# main.net
KiCad netlist of a schematic drawn in Altium Designer
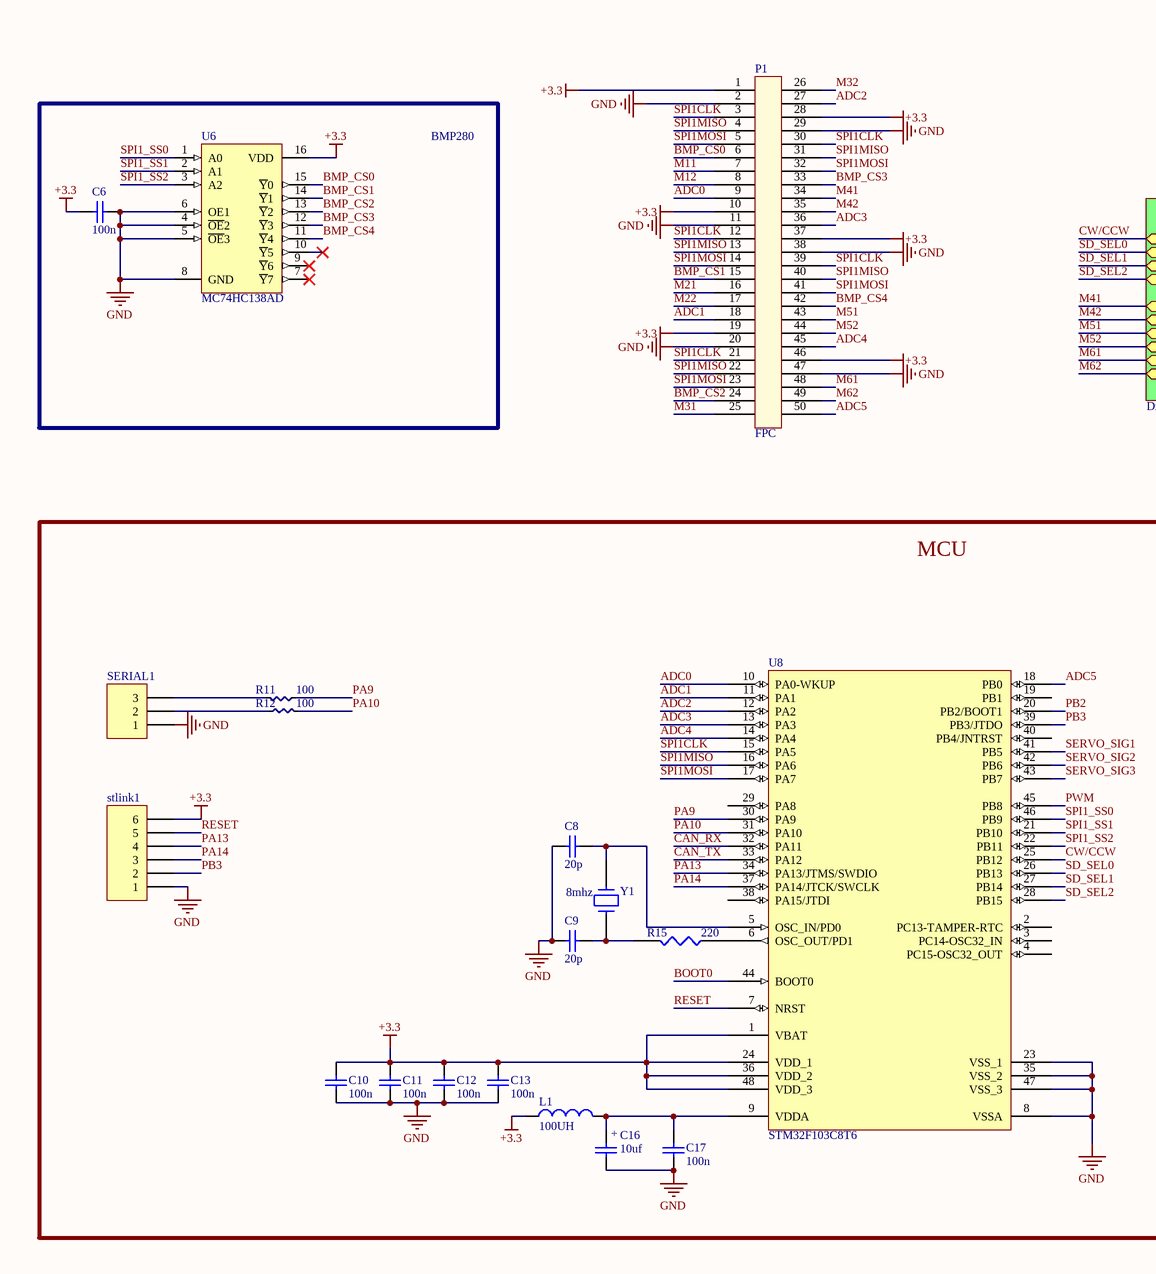
[diagram p0: main.SchDoc, left]
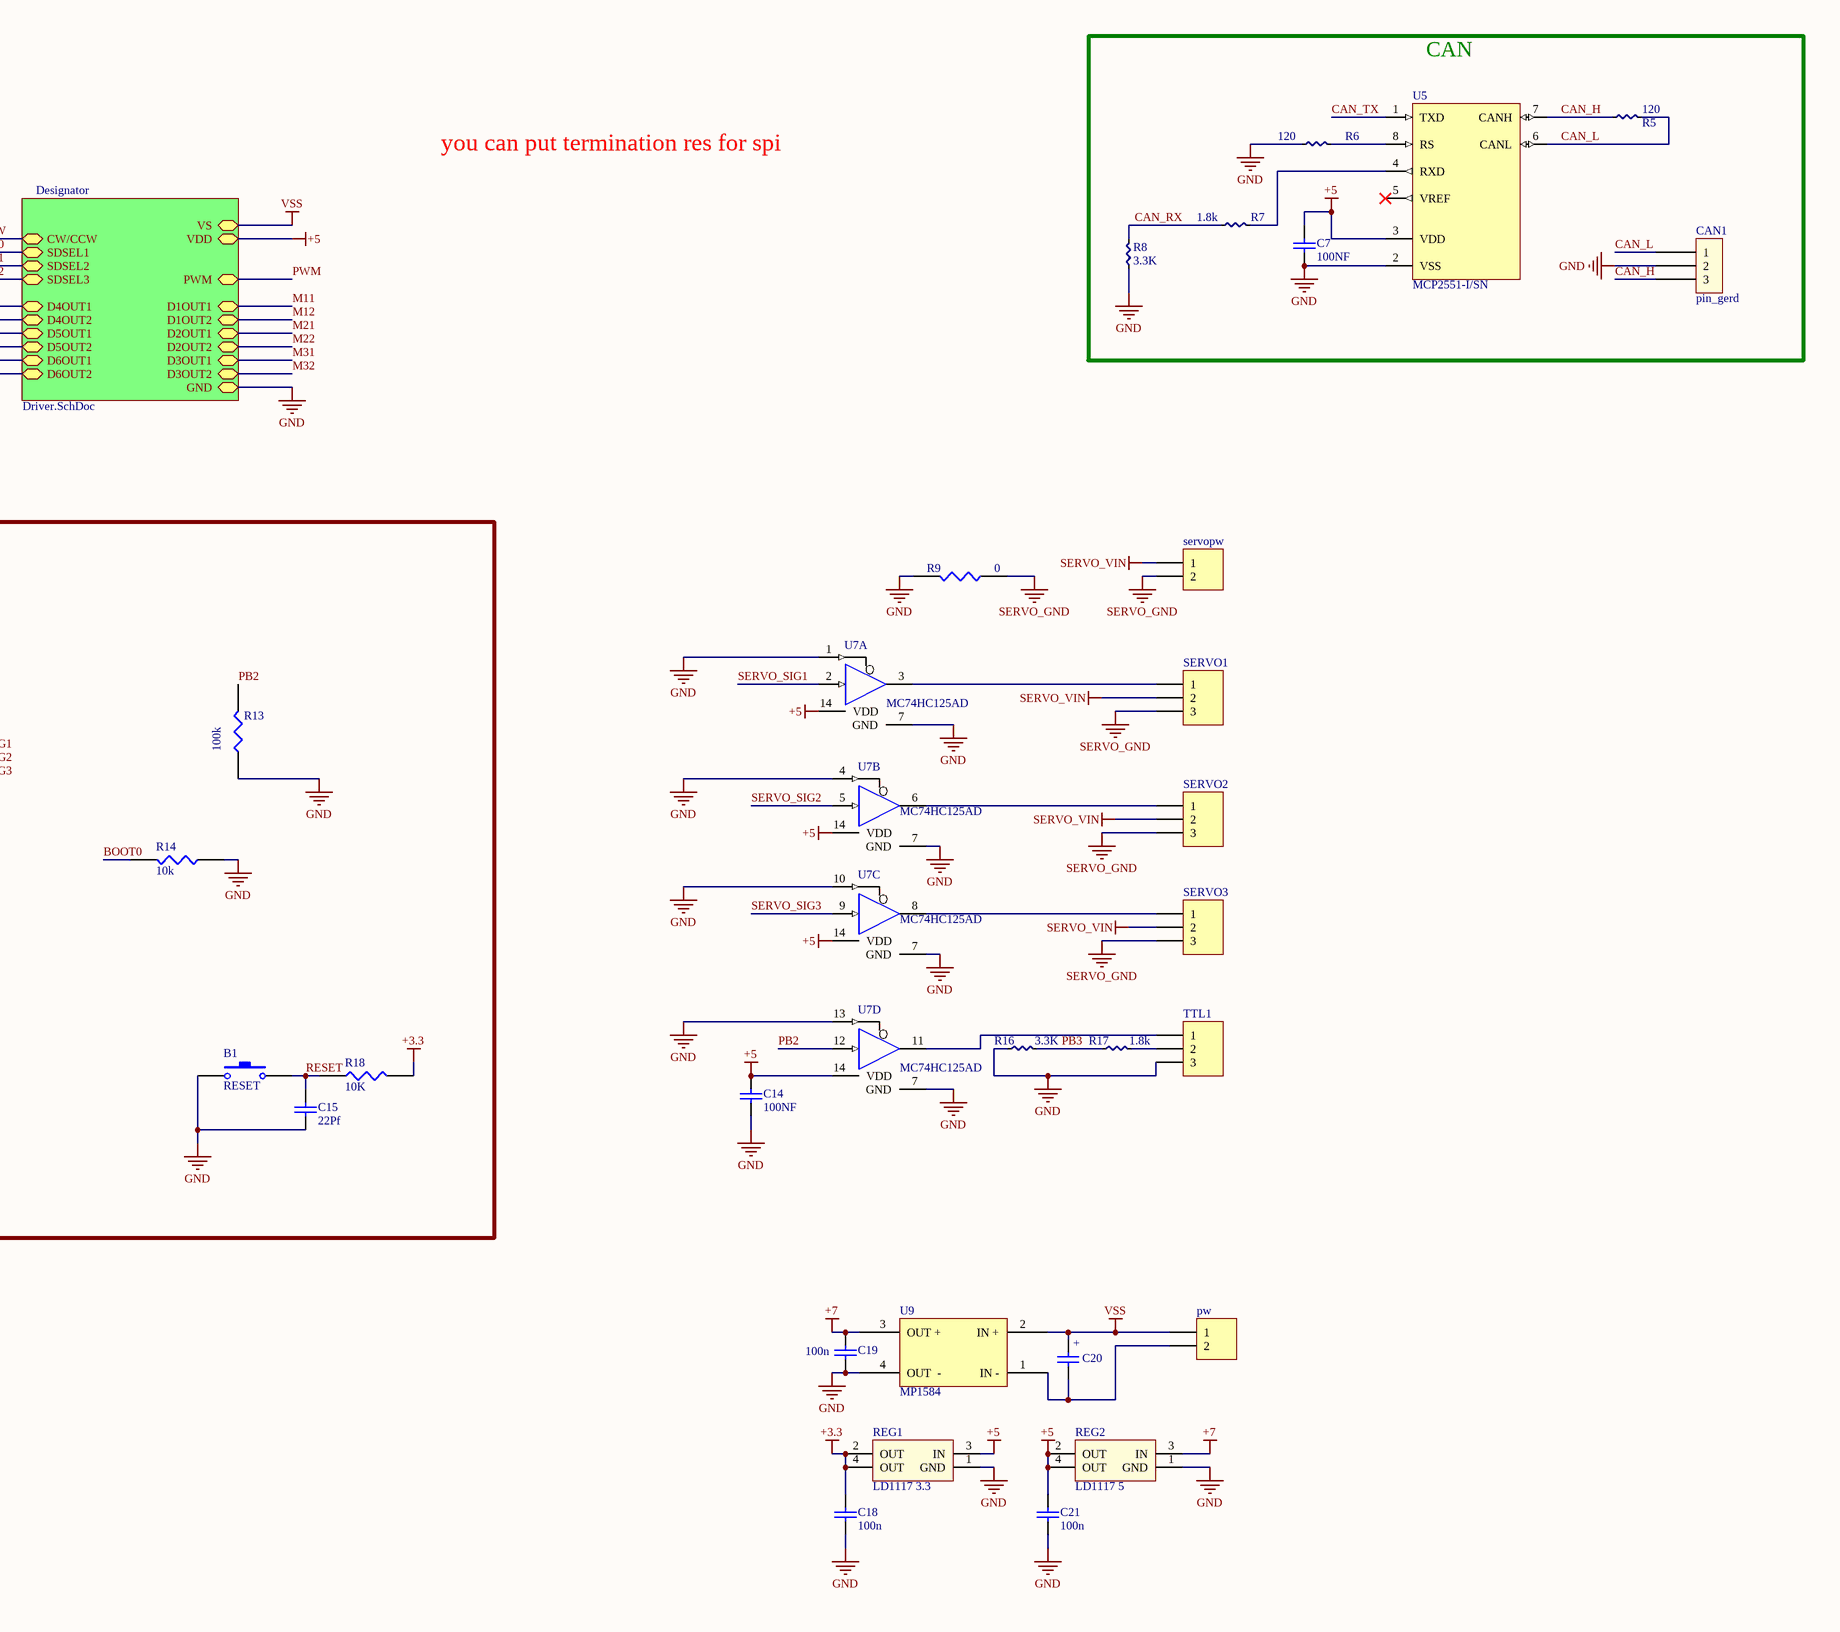
[diagram p1: main.SchDoc, right]

(export (version "E")
  (design (tool "Eeschema 10.0.6"))
  (components
    (comp (ref "B1")
      (value "RESET")
      (footprint "SMD PUSH BUTTON")
      (libsource (lib "AMINLIB") (part "SMD_PUSH_BUTTON"))
    )
    (comp (ref "C6")
      (value "100n")
      (footprint "MY_CAP_SMD_0805")
      (libsource (lib "AMINLIB") (part "CAP SMD"))
    )
    (comp (ref "C7")
      (value "100NF")
      (footprint "MY_CAP_SMD_0805")
      (description "2.0 mm × 1.25 mm")
      (libsource (lib "AMINLIB") (part "CAP SMD_0805"))
    )
    (comp (ref "C8") (value "20p") (footprint "MY_CAP_SMD_0805") (libsource (lib "AMINLIB") (part "CAP SMD")))
    (comp (ref "C9") (value "20p") (footprint "MY_CAP_SMD_0805") (libsource (lib "AMINLIB") (part "CAP SMD")))
    (comp (ref "C10")
      (value "100n")
      (footprint "MY_CAP_SMD_0805")
      (libsource (lib "AMINLIB") (part "CAP SMD"))
    )
    (comp (ref "C11")
      (value "100n")
      (footprint "MY_CAP_SMD_0805")
      (libsource (lib "AMINLIB") (part "CAP SMD"))
    )
    (comp (ref "C12")
      (value "100n")
      (footprint "MY_CAP_SMD_0805")
      (libsource (lib "AMINLIB") (part "CAP SMD"))
    )
    (comp (ref "C13")
      (value "100n")
      (footprint "MY_CAP_SMD_0805")
      (libsource (lib "AMINLIB") (part "CAP SMD"))
    )
    (comp (ref "C14")
      (value "100NF")
      (footprint "MY_CAP_SMD_0805")
      (description "2.0 mm × 1.25 mm")
      (libsource (lib "AMINLIB") (part "CAP SMD_0805"))
    )
    (comp (ref "C15")
      (value "22Pf")
      (footprint "MY_CAP_SMD_0805")
      (libsource (lib "AMINLIB") (part "CAP SMD"))
    )
    (comp (ref "C16")
      (value "10uf")
      (footprint "MY_cap_smd10uf")
      (libsource (lib "AMINLIB") (part "cap_smd_10u"))
    )
    (comp (ref "C17")
      (value "100n")
      (footprint "MY_CAP_SMD_0805")
      (libsource (lib "AMINLIB") (part "CAP SMD"))
    )
    (comp (ref "C18")
      (value "100n")
      (footprint "MY_CAP_SMD_0805")
      (libsource (lib "AMINLIB") (part "CAP SMD"))
    )
    (comp (ref "C19")
      (value "100n")
      (footprint "MY_CAP_SMD_0805")
      (libsource (lib "AMINLIB") (part "CAP SMD"))
    )
    (comp (ref "C20")
      (value "Cap")
      (footprint "MY_CAP_SMD-C")
      (description "6X3.2MM")
      (libsource (lib "AMINLIB") (part "CAP_TANTAL_C"))
    )
    (comp (ref "C21")
      (value "100n")
      (footprint "MY_CAP_SMD_0805")
      (libsource (lib "AMINLIB") (part "CAP SMD"))
    )
    (comp (ref "CAN1")
      (value "pin_gerd")
      (footprint "MY_PINGERD3")
      (description "3pin")
      (libsource (lib "AMINLIB") (part "pin_gerd"))
    )
    (comp (ref "L1")
      (value "100UH")
      (footprint "MY_SMD_INDUCTOR")
      (libsource (lib "AMINLIB") (part "INDUCTOR SMD"))
    )
    (comp (ref "P1")
      (value "FPC")
      (footprint "FPC-50-POS-0.5-MM")
      (libsource (lib "HAND-MULTILAYER") (part "FPC-50-POS-0.5-MM"))
    )
    (comp (ref "pw")
      (value "Header 2")
      (footprint "My_1X02")
      (description "Header, 2-Pin")
      (fields (field (name "PUBLISHER") "Altium Limited"))
      (libsource (lib "AMINLIB") (part "Header 2"))
    )
    (comp (ref "R5")
      (value "120")
      (footprint "MY_RES_SMD_0805")
      (libsource (lib "AMINLIB") (part "RES SMD 0805"))
    )
    (comp (ref "R6")
      (value "120")
      (footprint "MY_RES_SMD_0805")
      (libsource (lib "AMINLIB") (part "RES SMD 0805"))
    )
    (comp (ref "R7")
      (value "1.8k")
      (footprint "MY_RES_SMD_0805")
      (libsource (lib "AMINLIB") (part "RES SMD 0805"))
    )
    (comp (ref "R8")
      (value "3.3K")
      (footprint "MY_RES_SMD_0805")
      (libsource (lib "AMINLIB") (part "RES SMD 0805"))
    )
    (comp (ref "R9") (value "0") (footprint "MY_RES_SMD_0805") (libsource (lib "AMINLIB") (part "RES SMD")))
    (comp (ref "R11")
      (value "100")
      (footprint "MY_RES_SMD_0805")
      (libsource (lib "AMINLIB") (part "RES SMD 0805"))
    )
    (comp (ref "R12")
      (value "100")
      (footprint "MY_RES_SMD_0805")
      (libsource (lib "AMINLIB") (part "RES SMD 0805"))
    )
    (comp (ref "R13")
      (value "100k")
      (footprint "MY_RES_SMD_0805")
      (libsource (lib "AMINLIB") (part "RES SMD"))
    )
    (comp (ref "R14")
      (value "10k")
      (footprint "MY_RES_SMD_0805")
      (libsource (lib "AMINLIB") (part "RES SMD"))
    )
    (comp (ref "R15")
      (value "220")
      (footprint "MY_RES_SMD_0805")
      (libsource (lib "AMINLIB") (part "RES SMD"))
    )
    (comp (ref "R16")
      (value "3.3K")
      (footprint "MY_RES_SMD_0805")
      (libsource (lib "AMINLIB") (part "RES SMD 0805"))
    )
    (comp (ref "R17")
      (value "1.8k")
      (footprint "MY_RES_SMD_0805")
      (libsource (lib "AMINLIB") (part "RES SMD 0805"))
    )
    (comp (ref "R18")
      (value "10K")
      (footprint "MY_RES_SMD_0805")
      (libsource (lib "AMINLIB") (part "RES SMD"))
    )
    (comp (ref "REG1")
      (value "LD1117 3.3")
      (footprint "MY_LD1117-3.3")
      (libsource (lib "AMINLIB") (part "LD1117 3.3"))
    )
    (comp (ref "REG2")
      (value "LD1117 5")
      (footprint "MY_LD1117-3.3")
      (libsource (lib "AMINLIB") (part "LD1117 3.3"))
    )
    (comp (ref "SERIAL1")
      (value "Header 3")
      (footprint "My_1X03")
      (description "Header, 3-Pin")
      (fields (field (name "PUBLISHER") "Altium Limited"))
      (libsource (lib "AMINLIB") (part "Header 3"))
    )
    (comp (ref "SERVO1")
      (value "Header 3")
      (footprint "My_1X03")
      (description "Header, 3-Pin")
      (fields (field (name "PUBLISHER") "Altium Limited"))
      (libsource (lib "") (part "Header 3_1"))
    )
    (comp (ref "SERVO2")
      (value "Header 3")
      (footprint "My_1X03")
      (description "Header, 3-Pin")
      (fields (field (name "PUBLISHER") "Altium Limited"))
      (libsource (lib "") (part "Header 3_1"))
    )
    (comp (ref "SERVO3")
      (value "Header 3")
      (footprint "My_1X03")
      (description "Header, 3-Pin")
      (fields (field (name "PUBLISHER") "Altium Limited"))
      (libsource (lib "") (part "Header 3_1"))
    )
    (comp (ref "servopw")
      (value "Header 2")
      (footprint "My_1X02")
      (description "Header, 2-Pin")
      (fields (field (name "PUBLISHER") "Altium Limited"))
      (libsource (lib "AMINLIB") (part "Header 2"))
    )
    (comp (ref "stlink1")
      (value "Header 6")
      (footprint "My_1X06")
      (description "Header, 6-Pin")
      (fields (field (name "PUBLISHER") "Altium Limited"))
      (libsource (lib "AMINLIB") (part "Header 6"))
    )
    (comp (ref "TTL1")
      (value "Header 3")
      (footprint "My_1X03")
      (description "Header, 3-Pin")
      (fields (field (name "PUBLISHER") "Altium Limited"))
      (libsource (lib "") (part "Header 3_1"))
    )
    (comp (ref "U5")
      (value "MCP2551-I/SN")
      (footprint "SOIC-SN8_N")
      (description "High-Speed CAN Transceiver, 8-Pin SOIC, Industrial Temperature")
      (fields (field (name "PUBLISHER") "Altium Limited"))
      (libsource (lib "Microchip Interface") (part "MCP2551-I/SN"))
    )
    (comp (ref "U6")
      (value "MC74HC138AD")
      (footprint "751B-03_N")
      (description "1-of-8 Decoder/Demultiplexer")
      (fields (field (name "PUBLISHER") "Altium Limited"))
      (libsource (lib "Motorola Logic Decoder Demux") (part "MC74HC138AD"))
    )
    (comp (ref "U7")
      (value "MC74HC125AD")
      (footprint "751A-02_N")
      (description "Quad 3-State Non-Inverting Buffer")
      (fields (field (name "PUBLISHER") "Altium Limited"))
      (libsource (lib "Motorola Logic Buffer Line Driver") (part "MC74HC125AD"))
    )
    (comp (ref "U8")
      (value "STM32F103C8T6")
      (footprint "LQFP48_N")
      (description "STM32 ARM-based 32-bit MCU with 64 Kbytes Flash, 48-pin LQFP, Industrial Temperature")
      (fields (field (name "PUBLISHER") "Altium Limited"))
      (libsource (lib "ST Microcontroller 32-Bit STM32") (part "STM32F103C8T6"))
    )
    (comp (ref "U9")
      (value "MP1584")
      (footprint "mp1584")
      (description "SWITCHING REGULATOR MODULE")
      (fields (field (name "PART") "MP1584EN-LF-Z"))
      (libsource (lib "AMINLIB") (part "MP1584"))
    )
    (comp (ref "Y1")
      (value "8mhz")
      (footprint "My_Crystal - SMD")
      (description "Crystal")
      (libsource (lib "AMINLIB") (part "CRYSTAL"))
    )
  )
  (nets
    (net (code "1") (name "+3.3") (class "Default")
      (node (ref "C10") (pin "2") (pinfunction "2_2") (pintype "passive"))
      (node (ref "C11") (pin "2") (pinfunction "2_2") (pintype "passive"))
      (node (ref "C12") (pin "2") (pinfunction "2_2") (pintype "passive"))
      (node (ref "C13") (pin "2") (pinfunction "2_2") (pintype "passive"))
      (node (ref "C18") (pin "2") (pinfunction "2_2") (pintype "passive"))
      (node (ref "C6") (pin "2") (pinfunction "2_2") (pintype "passive"))
      (node (ref "L1") (pin "1") (pinfunction "1_1") (pintype "passive"))
      (node (ref "P1") (pin "1") (pinfunction "1_1") (pintype "passive"))
      (node (ref "P1") (pin "10") (pinfunction "10_10") (pintype "passive"))
      (node (ref "P1") (pin "19") (pinfunction "19_19") (pintype "passive"))
      (node (ref "P1") (pin "28") (pinfunction "28_28") (pintype "passive"))
      (node (ref "P1") (pin "37") (pinfunction "37_37") (pintype "passive"))
      (node (ref "P1") (pin "46") (pinfunction "46_46") (pintype "passive"))
      (node (ref "R18") (pin "2") (pinfunction "2_2") (pintype "passive"))
      (node (ref "REG1") (pin "2") (pinfunction "OUT_2") (pintype "power_in"))
      (node (ref "REG1") (pin "4") (pinfunction "OUT_4") (pintype "power_in"))
      (node (ref "U6") (pin "16") (pinfunction "VDD_16") (pintype "power_in"))
      (node (ref "U8") (pin "1") (pinfunction "VBAT_1") (pintype "power_in"))
      (node (ref "U8") (pin "24") (pinfunction "VDD_1_24") (pintype "power_in"))
      (node (ref "U8") (pin "36") (pinfunction "VDD_2_36") (pintype "power_in"))
      (node (ref "U8") (pin "48") (pinfunction "VDD_3_48") (pintype "power_in"))
      (node (ref "stlink1") (pin "6") (pinfunction "6_6") (pintype "passive"))
    )
    (net (code "2") (name "+5") (class "Default")
      (node (ref "C14") (pin "2") (pinfunction "2_2") (pintype "passive"))
      (node (ref "C21") (pin "2") (pinfunction "2_2") (pintype "passive"))
      (node (ref "C7") (pin "2") (pinfunction "2_2") (pintype "passive"))
      (node (ref "REG1") (pin "3") (pinfunction "IN_3") (pintype "power_in"))
      (node (ref "REG2") (pin "2") (pinfunction "OUT_2") (pintype "power_in"))
      (node (ref "REG2") (pin "4") (pinfunction "OUT_4") (pintype "power_in"))
      (node (ref "U5") (pin "3") (pinfunction "VDD_3") (pintype "power_in"))
      (node (ref "U7") (pin "14") (pinfunction "VDD_14") (pintype "power_in"))
    )
    (net (code "3") (name "+7") (class "Default")
      (node (ref "C19") (pin "2") (pinfunction "2_2") (pintype "passive"))
      (node (ref "REG2") (pin "3") (pinfunction "IN_3") (pintype "power_in"))
      (node (ref "U9") (pin "3") (pinfunction "OUT_+_3") (pintype "passive"))
    )
    (net (code "4") (name "/ADC0") (class "Default")
      (node (ref "P1") (pin "9") (pinfunction "9_9") (pintype "passive"))
      (node (ref "U8") (pin "10") (pinfunction "PA0-WKUP_10") (pintype "bidirectional"))
    )
    (net (code "5") (name "/ADC1") (class "Default")
      (node (ref "P1") (pin "18") (pinfunction "18_18") (pintype "passive"))
      (node (ref "U8") (pin "11") (pinfunction "PA1_11") (pintype "bidirectional"))
    )
    (net (code "6") (name "/ADC2") (class "Default")
      (node (ref "P1") (pin "27") (pinfunction "27_27") (pintype "passive"))
      (node (ref "U8") (pin "12") (pinfunction "PA2_12") (pintype "bidirectional"))
    )
    (net (code "7") (name "/ADC3") (class "Default")
      (node (ref "P1") (pin "36") (pinfunction "36_36") (pintype "passive"))
      (node (ref "U8") (pin "13") (pinfunction "PA3_13") (pintype "bidirectional"))
    )
    (net (code "8") (name "/ADC4") (class "Default")
      (node (ref "P1") (pin "45") (pinfunction "45_45") (pintype "passive"))
      (node (ref "U8") (pin "14") (pinfunction "PA4_14") (pintype "bidirectional"))
    )
    (net (code "9") (name "/ADC5") (class "Default")
      (node (ref "P1") (pin "50") (pinfunction "50_50") (pintype "passive"))
      (node (ref "U8") (pin "18") (pinfunction "PB0_18") (pintype "bidirectional"))
    )
    (net (code "10") (name "/BMP_CS0") (class "Default")
      (node (ref "P1") (pin "6") (pinfunction "6_6") (pintype "passive"))
      (node (ref "U6") (pin "15") (pinfunction "~{Y}0_15") (pintype "output"))
    )
    (net (code "11") (name "/BMP_CS1") (class "Default")
      (node (ref "P1") (pin "15") (pinfunction "15_15") (pintype "passive"))
      (node (ref "U6") (pin "14") (pinfunction "~{Y}1_14") (pintype "output"))
    )
    (net (code "12") (name "/BMP_CS2") (class "Default")
      (node (ref "P1") (pin "24") (pinfunction "24_24") (pintype "passive"))
      (node (ref "U6") (pin "13") (pinfunction "~{Y}2_13") (pintype "output"))
    )
    (net (code "13") (name "/BMP_CS3") (class "Default")
      (node (ref "P1") (pin "33") (pinfunction "33_33") (pintype "passive"))
      (node (ref "U6") (pin "12") (pinfunction "~{Y}3_12") (pintype "output"))
    )
    (net (code "14") (name "/BMP_CS4") (class "Default")
      (node (ref "P1") (pin "42") (pinfunction "42_42") (pintype "passive"))
      (node (ref "U6") (pin "11") (pinfunction "~{Y}4_11") (pintype "output"))
    )
    (net (code "15") (name "/BOOT0") (class "Default")
      (node (ref "R14") (pin "2") (pinfunction "2_2") (pintype "passive"))
      (node (ref "U8") (pin "44") (pinfunction "BOOT0_44") (pintype "input"))
    )
    (net (code "16") (name "/CAN_H") (class "Default")
      (node (ref "CAN1") (pin "3") (pinfunction "3_3") (pintype "passive"))
      (node (ref "R5") (pin "1") (pinfunction "1_1") (pintype "passive"))
      (node (ref "U5") (pin "7") (pinfunction "CANH_7") (pintype "bidirectional"))
    )
    (net (code "17") (name "/CAN_L") (class "Default")
      (node (ref "CAN1") (pin "1") (pinfunction "1_1") (pintype "passive"))
      (node (ref "R5") (pin "2") (pinfunction "2_2") (pintype "passive"))
      (node (ref "U5") (pin "6") (pinfunction "CANL_6") (pintype "bidirectional"))
    )
    (net (code "18") (name "/CAN_RX") (class "Default")
      (node (ref "R7") (pin "1") (pinfunction "1_1") (pintype "passive"))
      (node (ref "R8") (pin "2") (pinfunction "2_2") (pintype "passive"))
      (node (ref "U8") (pin "32") (pinfunction "PA11_32") (pintype "bidirectional"))
    )
    (net (code "19") (name "/CAN_TX") (class "Default")
      (node (ref "U5") (pin "1") (pinfunction "TXD_1") (pintype "input"))
      (node (ref "U8") (pin "33") (pinfunction "PA12_33") (pintype "bidirectional"))
    )
    (net (code "20") (name "/CW{slash}CCW") (class "Default")
      (node (ref "U8") (pin "25") (pinfunction "PB12_25") (pintype "bidirectional"))
    )
    (net (code "21") (name "/M11") (class "Default")
      (node (ref "P1") (pin "7") (pinfunction "7_7") (pintype "passive"))
    )
    (net (code "22") (name "/M12") (class "Default")
      (node (ref "P1") (pin "8") (pinfunction "8_8") (pintype "passive"))
    )
    (net (code "23") (name "/M21") (class "Default")
      (node (ref "P1") (pin "16") (pinfunction "16_16") (pintype "passive"))
    )
    (net (code "24") (name "/M22") (class "Default")
      (node (ref "P1") (pin "17") (pinfunction "17_17") (pintype "passive"))
    )
    (net (code "25") (name "/M31") (class "Default")
      (node (ref "P1") (pin "25") (pinfunction "25_25") (pintype "passive"))
    )
    (net (code "26") (name "/M32") (class "Default")
      (node (ref "P1") (pin "26") (pinfunction "26_26") (pintype "passive"))
    )
    (net (code "27") (name "/M41") (class "Default")
      (node (ref "P1") (pin "34") (pinfunction "34_34") (pintype "passive"))
    )
    (net (code "28") (name "/M42") (class "Default")
      (node (ref "P1") (pin "35") (pinfunction "35_35") (pintype "passive"))
    )
    (net (code "29") (name "/M51") (class "Default")
      (node (ref "P1") (pin "43") (pinfunction "43_43") (pintype "passive"))
    )
    (net (code "30") (name "/M52") (class "Default")
      (node (ref "P1") (pin "44") (pinfunction "44_44") (pintype "passive"))
    )
    (net (code "31") (name "/M61") (class "Default")
      (node (ref "P1") (pin "48") (pinfunction "48_48") (pintype "passive"))
    )
    (net (code "32") (name "/M62") (class "Default")
      (node (ref "P1") (pin "49") (pinfunction "49_49") (pintype "passive"))
    )
    (net (code "33") (name "/PA9") (class "Default")
      (node (ref "R11") (pin "1") (pinfunction "1_1") (pintype "passive"))
      (node (ref "U8") (pin "30") (pinfunction "PA9_30") (pintype "bidirectional"))
    )
    (net (code "34") (name "/PA10") (class "Default")
      (node (ref "R12") (pin "2") (pinfunction "2_2") (pintype "passive"))
      (node (ref "U8") (pin "31") (pinfunction "PA10_31") (pintype "bidirectional"))
    )
    (net (code "35") (name "/PA13") (class "Default")
      (node (ref "U8") (pin "34") (pinfunction "PA13/JTMS/SWDIO_34") (pintype "bidirectional"))
      (node (ref "stlink1") (pin "4") (pinfunction "4_4") (pintype "passive"))
    )
    (net (code "36") (name "/PA14") (class "Default")
      (node (ref "U8") (pin "37") (pinfunction "PA14/JTCK/SWCLK_37") (pintype "bidirectional"))
      (node (ref "stlink1") (pin "3") (pinfunction "3_3") (pintype "passive"))
    )
    (net (code "37") (name "/PB2") (class "Default")
      (node (ref "R13") (pin "2") (pinfunction "2_2") (pintype "passive"))
      (node (ref "U7") (pin "12") (pinfunction "A_12") (pintype "input"))
      (node (ref "U8") (pin "20") (pinfunction "PB2/BOOT1_20") (pintype "bidirectional"))
    )
    (net (code "38") (name "/PB3") (class "Default")
      (node (ref "R16") (pin "2") (pinfunction "2_2") (pintype "passive"))
      (node (ref "R17") (pin "1") (pinfunction "1_1") (pintype "passive"))
      (node (ref "U8") (pin "39") (pinfunction "PB3/JTDO_39") (pintype "bidirectional"))
      (node (ref "stlink1") (pin "2") (pinfunction "2_2") (pintype "passive"))
    )
    (net (code "39") (name "/PWM") (class "Default")
      (node (ref "U8") (pin "45") (pinfunction "PB8_45") (pintype "bidirectional"))
    )
    (net (code "40") (name "/RESET") (class "Default")
      (node (ref "B1") (pin "2") (pinfunction "2_2") (pintype "passive"))
      (node (ref "C15") (pin "2") (pinfunction "2_2") (pintype "passive"))
      (node (ref "R18") (pin "1") (pinfunction "1_1") (pintype "passive"))
      (node (ref "U8") (pin "7") (pinfunction "NRST_7") (pintype "bidirectional"))
      (node (ref "stlink1") (pin "5") (pinfunction "5_5") (pintype "passive"))
    )
    (net (code "41") (name "/SD_SEL0") (class "Default")
      (node (ref "U8") (pin "26") (pinfunction "PB13_26") (pintype "bidirectional"))
    )
    (net (code "42") (name "/SD_SEL1") (class "Default")
      (node (ref "U8") (pin "27") (pinfunction "PB14_27") (pintype "bidirectional"))
    )
    (net (code "43") (name "/SD_SEL2") (class "Default")
      (node (ref "U8") (pin "28") (pinfunction "PB15_28") (pintype "bidirectional"))
    )
    (net (code "44") (name "/SERVO_SIG1") (class "Default")
      (node (ref "U7") (pin "2") (pinfunction "A_2") (pintype "input"))
      (node (ref "U8") (pin "41") (pinfunction "PB5_41") (pintype "bidirectional"))
    )
    (net (code "45") (name "/SERVO_SIG2") (class "Default")
      (node (ref "U7") (pin "5") (pinfunction "A_5") (pintype "input"))
      (node (ref "U8") (pin "42") (pinfunction "PB6_42") (pintype "bidirectional"))
    )
    (net (code "46") (name "/SERVO_SIG3") (class "Default")
      (node (ref "U7") (pin "9") (pinfunction "A_9") (pintype "input"))
      (node (ref "U8") (pin "43") (pinfunction "PB7_43") (pintype "bidirectional"))
    )
    (net (code "47") (name "/SPI1CLK") (class "Default")
      (node (ref "P1") (pin "12") (pinfunction "12_12") (pintype "passive"))
      (node (ref "P1") (pin "21") (pinfunction "21_21") (pintype "passive"))
      (node (ref "P1") (pin "3") (pinfunction "3_3") (pintype "passive"))
      (node (ref "P1") (pin "30") (pinfunction "30_30") (pintype "passive"))
      (node (ref "P1") (pin "39") (pinfunction "39_39") (pintype "passive"))
      (node (ref "U8") (pin "15") (pinfunction "PA5_15") (pintype "bidirectional"))
    )
    (net (code "48") (name "/SPI1MISO") (class "Default")
      (node (ref "P1") (pin "13") (pinfunction "13_13") (pintype "passive"))
      (node (ref "P1") (pin "22") (pinfunction "22_22") (pintype "passive"))
      (node (ref "P1") (pin "31") (pinfunction "31_31") (pintype "passive"))
      (node (ref "P1") (pin "4") (pinfunction "4_4") (pintype "passive"))
      (node (ref "P1") (pin "40") (pinfunction "40_40") (pintype "passive"))
      (node (ref "U8") (pin "16") (pinfunction "PA6_16") (pintype "bidirectional"))
    )
    (net (code "49") (name "/SPI1MOSI") (class "Default")
      (node (ref "P1") (pin "14") (pinfunction "14_14") (pintype "passive"))
      (node (ref "P1") (pin "23") (pinfunction "23_23") (pintype "passive"))
      (node (ref "P1") (pin "32") (pinfunction "32_32") (pintype "passive"))
      (node (ref "P1") (pin "41") (pinfunction "41_41") (pintype "passive"))
      (node (ref "P1") (pin "5") (pinfunction "5_5") (pintype "passive"))
      (node (ref "U8") (pin "17") (pinfunction "PA7_17") (pintype "bidirectional"))
    )
    (net (code "50") (name "/SPI1_SS0") (class "Default")
      (node (ref "U6") (pin "1") (pinfunction "A0_1") (pintype "input"))
      (node (ref "U8") (pin "46") (pinfunction "PB9_46") (pintype "bidirectional"))
    )
    (net (code "51") (name "/SPI1_SS1") (class "Default")
      (node (ref "U6") (pin "2") (pinfunction "A1_2") (pintype "input"))
      (node (ref "U8") (pin "21") (pinfunction "PB10_21") (pintype "bidirectional"))
    )
    (net (code "52") (name "/SPI1_SS2") (class "Default")
      (node (ref "U6") (pin "3") (pinfunction "A2_3") (pintype "input"))
      (node (ref "U8") (pin "22") (pinfunction "PB11_22") (pintype "bidirectional"))
    )
    (net (code "53") (name "GND") (class "Default")
      (node (ref "B1") (pin "1") (pinfunction "1_1") (pintype "passive"))
      (node (ref "C10") (pin "1") (pinfunction "1_1") (pintype "passive"))
      (node (ref "C11") (pin "1") (pinfunction "1_1") (pintype "passive"))
      (node (ref "C12") (pin "1") (pinfunction "1_1") (pintype "passive"))
      (node (ref "C13") (pin "1") (pinfunction "1_1") (pintype "passive"))
      (node (ref "C14") (pin "1") (pinfunction "1_1") (pintype "passive"))
      (node (ref "C15") (pin "1") (pinfunction "1_1") (pintype "passive"))
      (node (ref "C16") (pin "-") (pinfunction "-_-") (pintype "passive"))
      (node (ref "C17") (pin "1") (pinfunction "1_1") (pintype "passive"))
      (node (ref "C18") (pin "1") (pinfunction "1_1") (pintype "passive"))
      (node (ref "C19") (pin "1") (pinfunction "1_1") (pintype "passive"))
      (node (ref "C21") (pin "1") (pinfunction "1_1") (pintype "passive"))
      (node (ref "C6") (pin "1") (pinfunction "1_1") (pintype "passive"))
      (node (ref "C7") (pin "1") (pinfunction "1_1") (pintype "passive"))
      (node (ref "C8") (pin "2") (pinfunction "2_2") (pintype "passive"))
      (node (ref "C9") (pin "1") (pinfunction "1_1") (pintype "passive"))
      (node (ref "CAN1") (pin "2") (pinfunction "2_2") (pintype "passive"))
      (node (ref "P1") (pin "11") (pinfunction "11_11") (pintype "passive"))
      (node (ref "P1") (pin "2") (pinfunction "2_2") (pintype "passive"))
      (node (ref "P1") (pin "20") (pinfunction "20_20") (pintype "passive"))
      (node (ref "P1") (pin "29") (pinfunction "29_29") (pintype "passive"))
      (node (ref "P1") (pin "38") (pinfunction "38_38") (pintype "passive"))
      (node (ref "P1") (pin "47") (pinfunction "47_47") (pintype "passive"))
      (node (ref "R13") (pin "1") (pinfunction "1_1") (pintype "passive"))
      (node (ref "R14") (pin "1") (pinfunction "1_1") (pintype "passive"))
      (node (ref "R16") (pin "1") (pinfunction "1_1") (pintype "passive"))
      (node (ref "R6") (pin "1") (pinfunction "1_1") (pintype "passive"))
      (node (ref "R8") (pin "1") (pinfunction "1_1") (pintype "passive"))
      (node (ref "R9") (pin "2") (pinfunction "2_2") (pintype "passive"))
      (node (ref "REG1") (pin "1") (pinfunction "GND_1") (pintype "power_in"))
      (node (ref "REG2") (pin "1") (pinfunction "GND_1") (pintype "power_in"))
      (node (ref "SERIAL1") (pin "1") (pinfunction "1_1") (pintype "passive"))
      (node (ref "TTL1") (pin "3") (pinfunction "3_3") (pintype "passive"))
      (node (ref "U5") (pin "2") (pinfunction "VSS_2") (pintype "power_in"))
      (node (ref "U6") (pin "4") (pinfunction "~{OE}2_4") (pintype "input"))
      (node (ref "U6") (pin "5") (pinfunction "~{OE}3_5") (pintype "input"))
      (node (ref "U6") (pin "6") (pinfunction "OE1_6") (pintype "input"))
      (node (ref "U6") (pin "8") (pinfunction "GND_8") (pintype "power_in"))
      (node (ref "U7") (pin "1") (pinfunction "~{OE}_1") (pintype "input"))
      (node (ref "U7") (pin "10") (pinfunction "~{OE}_10") (pintype "input"))
      (node (ref "U7") (pin "13") (pinfunction "~{OE}_13") (pintype "input"))
      (node (ref "U7") (pin "4") (pinfunction "~{OE}_4") (pintype "input"))
      (node (ref "U7") (pin "7") (pinfunction "GND_7") (pintype "power_in"))
      (node (ref "U8") (pin "23") (pinfunction "VSS_1_23") (pintype "power_in"))
      (node (ref "U8") (pin "35") (pinfunction "VSS_2_35") (pintype "power_in"))
      (node (ref "U8") (pin "47") (pinfunction "VSS_3_47") (pintype "power_in"))
      (node (ref "U8") (pin "8") (pinfunction "VSSA_8") (pintype "power_in"))
      (node (ref "U9") (pin "4") (pinfunction "OUT__-_4") (pintype "passive"))
      (node (ref "stlink1") (pin "1") (pinfunction "1_1") (pintype "passive"))
    )
    (net (code "54") (name "Net-(C9-Pad2)") (class "Default")
      (node (ref "C9") (pin "2") (pinfunction "2_2") (pintype "passive"))
      (node (ref "R15") (pin "2") (pinfunction "2_2") (pintype "passive"))
      (node (ref "Y1") (pin "1") (pinfunction "1_1") (pintype "passive"))
    )
    (net (code "55") (name "Net-(R11-Pad2)") (class "Default")
      (node (ref "R11") (pin "2") (pinfunction "2_2") (pintype "passive"))
      (node (ref "SERIAL1") (pin "3") (pinfunction "3_3") (pintype "passive"))
    )
    (net (code "56") (name "Net-(R12-Pad1)") (class "Default")
      (node (ref "R12") (pin "1") (pinfunction "1_1") (pintype "passive"))
      (node (ref "SERIAL1") (pin "2") (pinfunction "2_2") (pintype "passive"))
    )
    (net (code "57") (name "Net-(R17-Pad2)") (class "Default")
      (node (ref "R17") (pin "2") (pinfunction "2_2") (pintype "passive"))
      (node (ref "TTL1") (pin "2") (pinfunction "2_2") (pintype "passive"))
    )
    (net (code "58") (name "Net-(U5-RS)") (class "Default")
      (node (ref "R6") (pin "2") (pinfunction "2_2") (pintype "passive"))
      (node (ref "U5") (pin "8") (pinfunction "RS_8") (pintype "input"))
    )
    (net (code "59") (name "Net-(U5-RXD)") (class "Default")
      (node (ref "R7") (pin "2") (pinfunction "2_2") (pintype "passive"))
      (node (ref "U5") (pin "4") (pinfunction "RXD_4") (pintype "output"))
    )
    (net (code "60") (name "Net-(U7A-Y)") (class "Default")
      (node (ref "SERVO1") (pin "1") (pinfunction "1_1") (pintype "passive"))
      (node (ref "U7") (pin "3") (pinfunction "Y_3") (pintype "tri_state"))
    )
    (net (code "61") (name "Net-(U7B-Y)") (class "Default")
      (node (ref "SERVO2") (pin "1") (pinfunction "1_1") (pintype "passive"))
      (node (ref "U7") (pin "6") (pinfunction "Y_6") (pintype "tri_state"))
    )
    (net (code "62") (name "Net-(U7C-Y)") (class "Default")
      (node (ref "SERVO3") (pin "1") (pinfunction "1_1") (pintype "passive"))
      (node (ref "U7") (pin "8") (pinfunction "Y_8") (pintype "tri_state"))
    )
    (net (code "63") (name "Net-(U7D-Y)") (class "Default")
      (node (ref "TTL1") (pin "1") (pinfunction "1_1") (pintype "passive"))
      (node (ref "U7") (pin "11") (pinfunction "Y_11") (pintype "tri_state"))
    )
    (net (code "64") (name "Net-(U8-OSC_IN{slash}PD0)") (class "Default")
      (node (ref "C8") (pin "1") (pinfunction "1_1") (pintype "passive"))
      (node (ref "U8") (pin "5") (pinfunction "OSC_IN/PD0_5") (pintype "input"))
      (node (ref "Y1") (pin "2") (pinfunction "2_2") (pintype "passive"))
    )
    (net (code "65") (name "Net-(U8-OSC_OUT{slash}PD1)") (class "Default")
      (node (ref "R15") (pin "1") (pinfunction "1_1") (pintype "passive"))
      (node (ref "U8") (pin "6") (pinfunction "OSC_OUT/PD1_6") (pintype "output"))
    )
    (net (code "66") (name "Net-(U8-VDDA)") (class "Default")
      (node (ref "C16") (pin "+") (pinfunction "+_+") (pintype "passive"))
      (node (ref "C17") (pin "2") (pinfunction "2_2") (pintype "passive"))
      (node (ref "L1") (pin "2") (pinfunction "2_2") (pintype "passive"))
      (node (ref "U8") (pin "9") (pinfunction "VDDA_9") (pintype "power_in"))
    )
    (net (code "67") (name "Net-(U9-IN_-)") (class "Default")
      (node (ref "C20") (pin "-") (pinfunction "-_-") (pintype "passive"))
      (node (ref "U9") (pin "1") (pinfunction "IN_-_1") (pintype "passive"))
      (node (ref "pw") (pin "2") (pinfunction "2_2") (pintype "passive"))
    )
    (net (code "68") (name "SERVO_GND") (class "Default")
      (node (ref "R9") (pin "1") (pinfunction "1_1") (pintype "passive"))
      (node (ref "SERVO1") (pin "3") (pinfunction "3_3") (pintype "passive"))
      (node (ref "SERVO2") (pin "3") (pinfunction "3_3") (pintype "passive"))
      (node (ref "SERVO3") (pin "3") (pinfunction "3_3") (pintype "passive"))
      (node (ref "servopw") (pin "2") (pinfunction "2_2") (pintype "passive"))
    )
    (net (code "69") (name "SERVO_VIN") (class "Default")
      (node (ref "SERVO1") (pin "2") (pinfunction "2_2") (pintype "passive"))
      (node (ref "SERVO2") (pin "2") (pinfunction "2_2") (pintype "passive"))
      (node (ref "SERVO3") (pin "2") (pinfunction "2_2") (pintype "passive"))
      (node (ref "servopw") (pin "1") (pinfunction "1_1") (pintype "passive"))
    )
    (net (code "70") (name "VSS") (class "Default")
      (node (ref "C20") (pin "+") (pinfunction "+_+") (pintype "passive"))
      (node (ref "U9") (pin "2") (pinfunction "IN_+_2") (pintype "passive"))
      (node (ref "pw") (pin "1") (pinfunction "1_1") (pintype "passive"))
    )
    (net (code "71") (name "unconnected-(U5-VREF-Pad5)") (class "Default")
      (node (ref "U5") (pin "5") (pinfunction "VREF_5") (pintype "output+no_connect"))
    )
    (net (code "72") (name "unconnected-(U6-~{Y}5-Pad10)") (class "Default")
      (node (ref "U6") (pin "10") (pinfunction "~{Y}5_10") (pintype "output+no_connect"))
    )
    (net (code "73") (name "unconnected-(U6-~{Y}6-Pad9)") (class "Default")
      (node (ref "U6") (pin "9") (pinfunction "~{Y}6_9") (pintype "output+no_connect"))
    )
    (net (code "74") (name "unconnected-(U6-~{Y}7-Pad7)") (class "Default")
      (node (ref "U6") (pin "7") (pinfunction "~{Y}7_7") (pintype "output+no_connect"))
    )
    (net (code "75") (name "unconnected-(U8-PA8-Pad29)") (class "Default")
      (node (ref "U8") (pin "29") (pinfunction "PA8_29") (pintype "bidirectional"))
    )
    (net (code "76") (name "unconnected-(U8-PA15{slash}JTDI-Pad38)") (class "Default")
      (node (ref "U8") (pin "38") (pinfunction "PA15/JTDI_38") (pintype "bidirectional"))
    )
    (net (code "77") (name "unconnected-(U8-PB1-Pad19)") (class "Default")
      (node (ref "U8") (pin "19") (pinfunction "PB1_19") (pintype "bidirectional"))
    )
    (net (code "78") (name "unconnected-(U8-PB4{slash}JNTRST-Pad40)") (class "Default")
      (node (ref "U8") (pin "40") (pinfunction "PB4/JNTRST_40") (pintype "bidirectional"))
    )
    (net (code "79") (name "unconnected-(U8-PC13-TAMPER-RTC-Pad2)") (class "Default")
      (node (ref "U8") (pin "2") (pinfunction "PC13-TAMPER-RTC_2") (pintype "bidirectional"))
    )
    (net (code "80") (name "unconnected-(U8-PC14-OSC32_IN-Pad3)") (class "Default")
      (node (ref "U8") (pin "3") (pinfunction "PC14-OSC32_IN_3") (pintype "bidirectional"))
    )
    (net (code "81") (name "unconnected-(U8-PC15-OSC32_OUT-Pad4)") (class "Default")
      (node (ref "U8") (pin "4") (pinfunction "PC15-OSC32_OUT_4") (pintype "bidirectional"))
    )
  )
)
